# bq25505V1.net
KiCad netlist of a schematic drawn in EAGLE
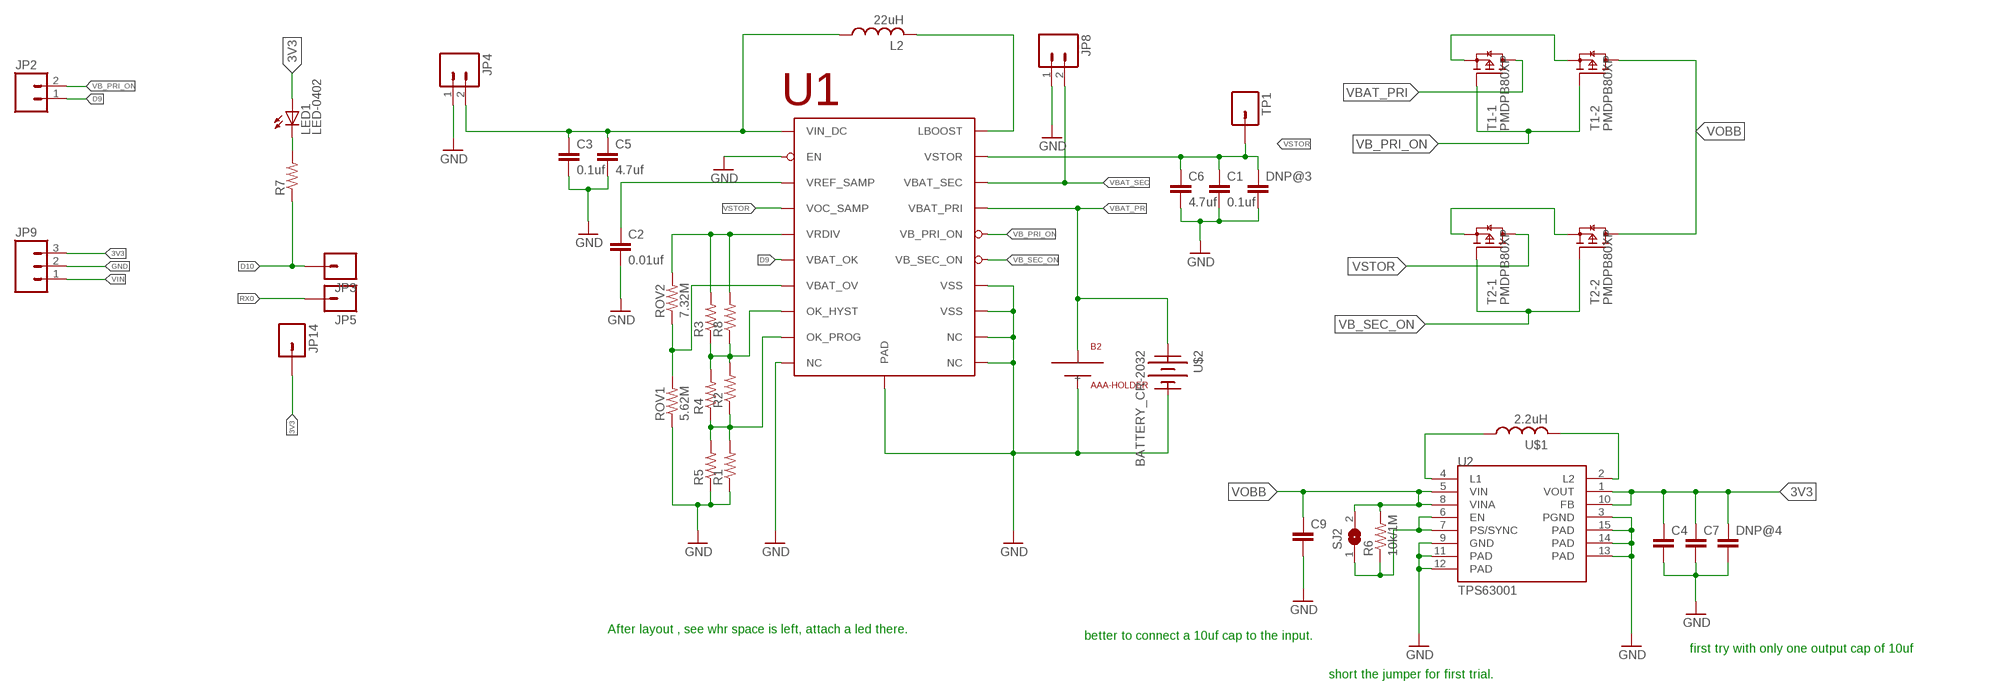
[diagram p0: schematic, sheet 1]

(export (version "E")
  (design (tool "Eeschema 10.0.6"))
  (components
    (comp (ref "B2")
      (value "AAA-HOLDER")
      (footprint "eagle-import:AAA-BATTERY")
      (libsource (lib "eagle-import") (part "AAA-HOLDER"))
    )
    (comp (ref "C1")
      (value "0.1uf")
      (footprint "eagle-import:C0805")
      (libsource (lib "eagle-import") (part "C-EUC0805"))
    )
    (comp (ref "C2")
      (value "0.01uf")
      (footprint "eagle-import:C0805")
      (libsource (lib "eagle-import") (part "C-EUC0805"))
    )
    (comp (ref "C3")
      (value "0.1uf")
      (footprint "eagle-import:C0805")
      (libsource (lib "eagle-import") (part "C-EUC0805"))
    )
    (comp (ref "C4")
      (value "C-EUC0805")
      (footprint "eagle-import:C0805")
      (libsource (lib "eagle-import") (part "C-EUC0805"))
    )
    (comp (ref "C5")
      (value "4.7uf")
      (footprint "eagle-import:C0805")
      (libsource (lib "eagle-import") (part "C-EUC0805"))
    )
    (comp (ref "C6")
      (value "4.7uf")
      (footprint "eagle-import:C0805")
      (libsource (lib "eagle-import") (part "C-EUC0805"))
    )
    (comp (ref "C7")
      (value "C-EUC0805")
      (footprint "eagle-import:C0805")
      (libsource (lib "eagle-import") (part "C-EUC0805"))
    )
    (comp (ref "C9")
      (value "C-EUC0805")
      (footprint "eagle-import:C0805")
      (libsource (lib "eagle-import") (part "C-EUC0805"))
    )
    (comp (ref "DNP@3")
      (value "C-EUC0805")
      (footprint "eagle-import:C0805")
      (libsource (lib "eagle-import") (part "C-EUC0805"))
    )
    (comp (ref "DNP@4")
      (value "C-EUC0805")
      (footprint "eagle-import:C0805")
      (libsource (lib "eagle-import") (part "C-EUC0805"))
    )
    (comp (ref "JP2")
      (value "M02PTH")
      (footprint "eagle-import:1X02")
      (libsource (lib "eagle-import") (part "M02PTH"))
    )
    (comp (ref "JP3")
      (value "M01PTH")
      (footprint "eagle-import:1X01")
      (libsource (lib "eagle-import") (part "M01PTH"))
    )
    (comp (ref "JP4")
      (value "M02-JST-2-PTH-NO_SILK")
      (footprint "eagle-import:JST-2-PTH-NS")
      (libsource (lib "eagle-import") (part "M02-JST-2-PTH-NO_SILK"))
    )
    (comp (ref "JP5")
      (value "M01PTH")
      (footprint "eagle-import:1X01")
      (libsource (lib "eagle-import") (part "M01PTH"))
    )
    (comp (ref "JP8")
      (value "M02-JST-2-PTH-NO_SILK")
      (footprint "eagle-import:JST-2-PTH-NS")
      (libsource (lib "eagle-import") (part "M02-JST-2-PTH-NO_SILK"))
    )
    (comp (ref "JP9")
      (value "M03PTH")
      (footprint "eagle-import:1X03")
      (libsource (lib "eagle-import") (part "M03PTH"))
    )
    (comp (ref "JP14")
      (value "M01PTH")
      (footprint "eagle-import:1X01")
      (libsource (lib "eagle-import") (part "M01PTH"))
    )
    (comp (ref "L2")
      (value "22uH")
      (footprint "eagle-import:LPS6235")
      (libsource (lib "eagle-import") (part "LPS6235"))
    )
    (comp (ref "LED1")
      (value "LED-0402")
      (footprint "eagle-import:0402")
      (libsource (lib "eagle-import") (part "LED-0402"))
    )
    (comp (ref "R1")
      (value "R-US_R0603")
      (footprint "eagle-import:R0603")
      (libsource (lib "eagle-import") (part "R-US_R0603"))
    )
    (comp (ref "R2")
      (value "R-US_R0805")
      (footprint "eagle-import:R0805")
      (libsource (lib "eagle-import") (part "R-US_R0805"))
    )
    (comp (ref "R3")
      (value "R-US_R0603")
      (footprint "eagle-import:R0603")
      (libsource (lib "eagle-import") (part "R-US_R0603"))
    )
    (comp (ref "R4")
      (value "R-US_R1206")
      (footprint "eagle-import:R1206")
      (libsource (lib "eagle-import") (part "R-US_R1206"))
    )
    (comp (ref "R5")
      (value "R-US_R0603")
      (footprint "eagle-import:R0603")
      (libsource (lib "eagle-import") (part "R-US_R0603"))
    )
    (comp (ref "R6")
      (value "10k/1M")
      (footprint "eagle-import:R0805")
      (libsource (lib "eagle-import") (part "R-US_R0805"))
    )
    (comp (ref "R7")
      (value "R-US_R0603")
      (footprint "eagle-import:R0603")
      (libsource (lib "eagle-import") (part "resistor_R-US_R0603"))
    )
    (comp (ref "R8")
      (value "R-US_R0805")
      (footprint "eagle-import:R0805")
      (libsource (lib "eagle-import") (part "R-US_R0805"))
    )
    (comp (ref "ROV1")
      (value "5.62M")
      (footprint "eagle-import:R1206")
      (libsource (lib "eagle-import") (part "R-US_R1206"))
    )
    (comp (ref "ROV2")
      (value "7.32M")
      (footprint "eagle-import:R1206")
      (libsource (lib "eagle-import") (part "R-US_R1206"))
    )
    (comp (ref "SJ2") (value "SJ") (footprint "eagle-import:SJ") (libsource (lib "eagle-import") (part "SJ")))
    (comp (ref "T1")
      (value "PMDPB80XP")
      (footprint "eagle-import:SOT1118")
      (libsource (lib "eagle-import") (part "PMDPB80XP"))
    )
    (comp (ref "T2")
      (value "PMDPB80XP")
      (footprint "eagle-import:SOT1118")
      (libsource (lib "eagle-import") (part "PMDPB80XP"))
    )
    (comp (ref "TP1")
      (value "M01PTH")
      (footprint "eagle-import:1X01")
      (libsource (lib "eagle-import") (part "M01PTH"))
    )
    (comp (ref "U$1")
      (value "2.2uH")
      (footprint "eagle-import:LPS3010")
      (libsource (lib "eagle-import") (part "LPS3010"))
    )
    (comp (ref "U$2")
      (value "BATTERY_CR-2032")
      (footprint "eagle-import:BATTCON_20MM")
      (libsource (lib "eagle-import") (part "BATTERY_CR-2032"))
    )
    (comp (ref "U1")
      (value "BQ25505")
      (footprint "eagle-import:VQFN-20")
      (libsource (lib "eagle-import") (part "BQ25505"))
    )
    (comp (ref "U2")
      (value "TPS63001")
      (footprint "eagle-import:QFN-10_PAD")
      (libsource (lib "eagle-import") (part "TPS63001"))
    )
  )
  (nets
    (net (code "1") (name "3V3") (class "Default")
      (node (ref "C4") (pin "1") (pinfunction "1_1") (pintype "passive"))
      (node (ref "C7") (pin "1") (pinfunction "1_1") (pintype "passive"))
      (node (ref "DNP@4") (pin "1") (pinfunction "1_1") (pintype "passive"))
      (node (ref "JP14") (pin "1") (pinfunction "1_1") (pintype "passive"))
      (node (ref "JP9") (pin "3") (pinfunction "3_3") (pintype "passive"))
      (node (ref "LED1") (pin "P$1") (pinfunction "A_P$1") (pintype "passive"))
      (node (ref "U2") (pin "1") (pinfunction "VOUT_1") (pintype "passive"))
      (node (ref "U2") (pin "10") (pinfunction "FB_10") (pintype "passive"))
    )
    (net (code "2") (name "D9") (class "Default")
      (node (ref "JP2") (pin "1") (pinfunction "1_1") (pintype "passive"))
      (node (ref "U1") (pin "P$13") (pinfunction "VBAT_OK_P$13") (pintype "output"))
    )
    (net (code "3") (name "D10") (class "Default")
      (node (ref "JP3") (pin "1") (pinfunction "1_1") (pintype "passive"))
      (node (ref "R7") (pin "1") (pinfunction "1_1") (pintype "passive"))
    )
    (net (code "4") (name "GND") (class "Default")
      (node (ref "B2") (pin "P$2") (pinfunction "-_P$2") (pintype "output"))
      (node (ref "C1") (pin "2") (pinfunction "2_2") (pintype "passive"))
      (node (ref "C2") (pin "2") (pinfunction "2_2") (pintype "passive"))
      (node (ref "C3") (pin "2") (pinfunction "2_2") (pintype "passive"))
      (node (ref "C4") (pin "2") (pinfunction "2_2") (pintype "passive"))
      (node (ref "C5") (pin "2") (pinfunction "2_2") (pintype "passive"))
      (node (ref "C6") (pin "2") (pinfunction "2_2") (pintype "passive"))
      (node (ref "C7") (pin "2") (pinfunction "2_2") (pintype "passive"))
      (node (ref "C9") (pin "2") (pinfunction "2_2") (pintype "passive"))
      (node (ref "DNP@3") (pin "2") (pinfunction "2_2") (pintype "passive"))
      (node (ref "DNP@4") (pin "2") (pinfunction "2_2") (pintype "passive"))
      (node (ref "JP4") (pin "1") (pinfunction "1_1") (pintype "passive"))
      (node (ref "JP8") (pin "1") (pinfunction "1_1") (pintype "passive"))
      (node (ref "JP9") (pin "2") (pinfunction "2_2") (pintype "passive"))
      (node (ref "R1") (pin "1") (pinfunction "1_1") (pintype "passive"))
      (node (ref "R5") (pin "1") (pinfunction "1_1") (pintype "passive"))
      (node (ref "ROV1") (pin "1") (pinfunction "1_1") (pintype "passive"))
      (node (ref "U$2") (pin "2") (pinfunction "-2_2") (pintype "power_in"))
      (node (ref "U1") (pin "P$1") (pinfunction "VSS_P$1") (pintype "power_in"))
      (node (ref "U1") (pin "P$15") (pinfunction "VSS_P$15") (pintype "power_in"))
      (node (ref "U1") (pin "P$16") (pinfunction "NC_P$16") (pintype "input"))
      (node (ref "U1") (pin "P$17") (pinfunction "NC_P$17") (pintype "input"))
      (node (ref "U1") (pin "P$21") (pinfunction "PAD_P$21") (pintype "power_in"))
      (node (ref "U1") (pin "P$5") (pinfunction "EN_P$5") (pintype "bidirectional"))
      (node (ref "U1") (pin "P$6") (pinfunction "NC_P$6") (pintype "input"))
      (node (ref "U2") (pin "11") (pinfunction "PAD_11") (pintype "power_in"))
      (node (ref "U2") (pin "12") (pinfunction "PAD_12") (pintype "power_in"))
      (node (ref "U2") (pin "13") (pinfunction "PAD_13") (pintype "power_in"))
      (node (ref "U2") (pin "14") (pinfunction "PAD_14") (pintype "power_in"))
      (node (ref "U2") (pin "15") (pinfunction "PAD_15") (pintype "power_in"))
      (node (ref "U2") (pin "3") (pinfunction "PGND_3") (pintype "passive"))
      (node (ref "U2") (pin "9") (pinfunction "GND_9") (pintype "power_in"))
    )
    (net (code "5") (name "Net-(L2-1)") (class "Default")
      (node (ref "C3") (pin "1") (pinfunction "1_1") (pintype "passive"))
      (node (ref "C5") (pin "1") (pinfunction "1_1") (pintype "passive"))
      (node (ref "JP4") (pin "2") (pinfunction "2_2") (pintype "passive"))
      (node (ref "L2") (pin "P$1") (pinfunction "1_P$1") (pintype "passive"))
      (node (ref "U1") (pin "P$2") (pinfunction "VIN_DC_P$2") (pintype "input"))
    )
    (net (code "6") (name "Net-(L2-2)") (class "Default")
      (node (ref "L2") (pin "P$2") (pinfunction "2_P$2") (pintype "passive"))
      (node (ref "U1") (pin "P$20") (pinfunction "LBOOST_P$20") (pintype "input"))
    )
    (net (code "7") (name "Net-(LED1-C)") (class "Default")
      (node (ref "LED1") (pin "P$2") (pinfunction "C_P$2") (pintype "passive"))
      (node (ref "R7") (pin "2") (pinfunction "2_2") (pintype "passive"))
    )
    (net (code "8") (name "Net-(T1A-S)") (class "Default")
      (node (ref "T1") (pin "1") (pinfunction "S_1") (pintype "passive"))
      (node (ref "T1") (pin "4") (pinfunction "S_4") (pintype "passive"))
    )
    (net (code "9") (name "Net-(T2A-S)") (class "Default")
      (node (ref "T2") (pin "1") (pinfunction "S_1") (pintype "passive"))
      (node (ref "T2") (pin "4") (pinfunction "S_4") (pintype "passive"))
    )
    (net (code "10") (name "Net-(U$1-1)") (class "Default")
      (node (ref "U$1") (pin "P$1") (pinfunction "1_P$1") (pintype "passive"))
      (node (ref "U2") (pin "4") (pinfunction "L1_4") (pintype "power_in"))
    )
    (net (code "11") (name "Net-(U$1-2)") (class "Default")
      (node (ref "U$1") (pin "P$2") (pinfunction "2_P$2") (pintype "passive"))
      (node (ref "U2") (pin "2") (pinfunction "L2_2") (pintype "passive"))
    )
    (net (code "12") (name "Net-(U1-OK_HYST)") (class "Default")
      (node (ref "R2") (pin "2") (pinfunction "2_2") (pintype "passive"))
      (node (ref "R3") (pin "1") (pinfunction "1_1") (pintype "passive"))
      (node (ref "R4") (pin "2") (pinfunction "2_2") (pintype "passive"))
      (node (ref "R8") (pin "1") (pinfunction "1_1") (pintype "passive"))
      (node (ref "U1") (pin "P$11") (pinfunction "OK_HYST_P$11") (pintype "input"))
    )
    (net (code "13") (name "Net-(U1-OK_PROG)") (class "Default")
      (node (ref "R1") (pin "2") (pinfunction "2_2") (pintype "passive"))
      (node (ref "R2") (pin "1") (pinfunction "1_1") (pintype "passive"))
      (node (ref "R4") (pin "1") (pinfunction "1_1") (pintype "passive"))
      (node (ref "R5") (pin "2") (pinfunction "2_2") (pintype "passive"))
      (node (ref "U1") (pin "P$12") (pinfunction "OK_PROG_P$12") (pintype "input"))
    )
    (net (code "14") (name "Net-(U1-VBAT_OV)") (class "Default")
      (node (ref "ROV1") (pin "2") (pinfunction "2_2") (pintype "passive"))
      (node (ref "ROV2") (pin "1") (pinfunction "1_1") (pintype "passive"))
      (node (ref "U1") (pin "P$7") (pinfunction "VBAT_OV_P$7") (pintype "bidirectional"))
    )
    (net (code "15") (name "Net-(U1-VRDIV)") (class "Default")
      (node (ref "R3") (pin "2") (pinfunction "2_2") (pintype "passive"))
      (node (ref "R8") (pin "2") (pinfunction "2_2") (pintype "passive"))
      (node (ref "ROV2") (pin "2") (pinfunction "2_2") (pintype "passive"))
      (node (ref "U1") (pin "P$8") (pinfunction "VRDIV_P$8") (pintype "output"))
    )
    (net (code "16") (name "Net-(U1-VREF_SAMP)") (class "Default")
      (node (ref "C2") (pin "1") (pinfunction "1_1") (pintype "passive"))
      (node (ref "U1") (pin "P$4") (pinfunction "VREF_SAMP_P$4") (pintype "input"))
    )
    (net (code "17") (name "Net-(U2-EN)") (class "Default")
      (node (ref "R6") (pin "1") (pinfunction "1_1") (pintype "passive"))
      (node (ref "SJ2") (pin "1") (pinfunction "1_1") (pintype "passive"))
      (node (ref "U2") (pin "6") (pinfunction "EN_6") (pintype "passive"))
      (node (ref "U2") (pin "7") (pinfunction "PS/SYNC_7") (pintype "power_in"))
    )
    (net (code "18") (name "RX0") (class "Default")
      (node (ref "JP5") (pin "1") (pinfunction "1_1") (pintype "passive"))
    )
    (net (code "19") (name "VBAT_PRI") (class "Default")
      (node (ref "B2") (pin "P$1") (pinfunction "+_P$1") (pintype "output"))
      (node (ref "T1") (pin "6") (pinfunction "D_6") (pintype "passive"))
      (node (ref "T1") (pin "7") (pinfunction "D_7") (pintype "passive"))
      (node (ref "U$2") (pin "1") (pinfunction "+2_1") (pintype "power_in"))
      (node (ref "U$2") (pin "3") (pinfunction "+2_3") (pintype "power_in"))
      (node (ref "U1") (pin "P$14") (pinfunction "VBAT_PRI_P$14") (pintype "input"))
    )
    (net (code "20") (name "VBAT_SEC") (class "Default")
      (node (ref "JP8") (pin "2") (pinfunction "2_2") (pintype "passive"))
      (node (ref "U1") (pin "P$18") (pinfunction "VBAT_SEC_P$18") (pintype "bidirectional"))
    )
    (net (code "21") (name "VB_PRI_ON") (class "Default")
      (node (ref "JP2") (pin "2") (pinfunction "2_2") (pintype "passive"))
      (node (ref "T1") (pin "2") (pinfunction "G_2") (pintype "passive"))
      (node (ref "T1") (pin "5") (pinfunction "G_5") (pintype "passive"))
      (node (ref "U1") (pin "P$10") (pinfunction "VB_PRI_ON_P$10") (pintype "output"))
    )
    (net (code "22") (name "VB_SEC_ON") (class "Default")
      (node (ref "T2") (pin "2") (pinfunction "G_2") (pintype "passive"))
      (node (ref "T2") (pin "5") (pinfunction "G_5") (pintype "passive"))
      (node (ref "U1") (pin "P$9") (pinfunction "VB_SEC_ON_P$9") (pintype "output"))
    )
    (net (code "23") (name "VIN") (class "Default")
      (node (ref "JP9") (pin "1") (pinfunction "1_1") (pintype "passive"))
    )
    (net (code "24") (name "VOBB") (class "Default")
      (node (ref "C9") (pin "1") (pinfunction "1_1") (pintype "passive"))
      (node (ref "R6") (pin "2") (pinfunction "2_2") (pintype "passive"))
      (node (ref "SJ2") (pin "2") (pinfunction "2_2") (pintype "passive"))
      (node (ref "T1") (pin "3") (pinfunction "D_3") (pintype "passive"))
      (node (ref "T1") (pin "8") (pinfunction "D_8") (pintype "passive"))
      (node (ref "T2") (pin "3") (pinfunction "D_3") (pintype "passive"))
      (node (ref "T2") (pin "8") (pinfunction "D_8") (pintype "passive"))
      (node (ref "U2") (pin "5") (pinfunction "VIN_5") (pintype "input"))
      (node (ref "U2") (pin "8") (pinfunction "VINA_8") (pintype "input"))
    )
    (net (code "25") (name "VSTOR") (class "Default")
      (node (ref "C1") (pin "1") (pinfunction "1_1") (pintype "passive"))
      (node (ref "C6") (pin "1") (pinfunction "1_1") (pintype "passive"))
      (node (ref "DNP@3") (pin "1") (pinfunction "1_1") (pintype "passive"))
      (node (ref "T2") (pin "6") (pinfunction "D_6") (pintype "passive"))
      (node (ref "T2") (pin "7") (pinfunction "D_7") (pintype "passive"))
      (node (ref "TP1") (pin "1") (pinfunction "1_1") (pintype "passive"))
      (node (ref "U1") (pin "P$19") (pinfunction "VSTOR_P$19") (pintype "output"))
      (node (ref "U1") (pin "P$3") (pinfunction "VOC_SAMP_P$3") (pintype "input"))
    )
  )
)
